# bsides2020.net
KiCad netlist of a schematic drawn in EAGLE
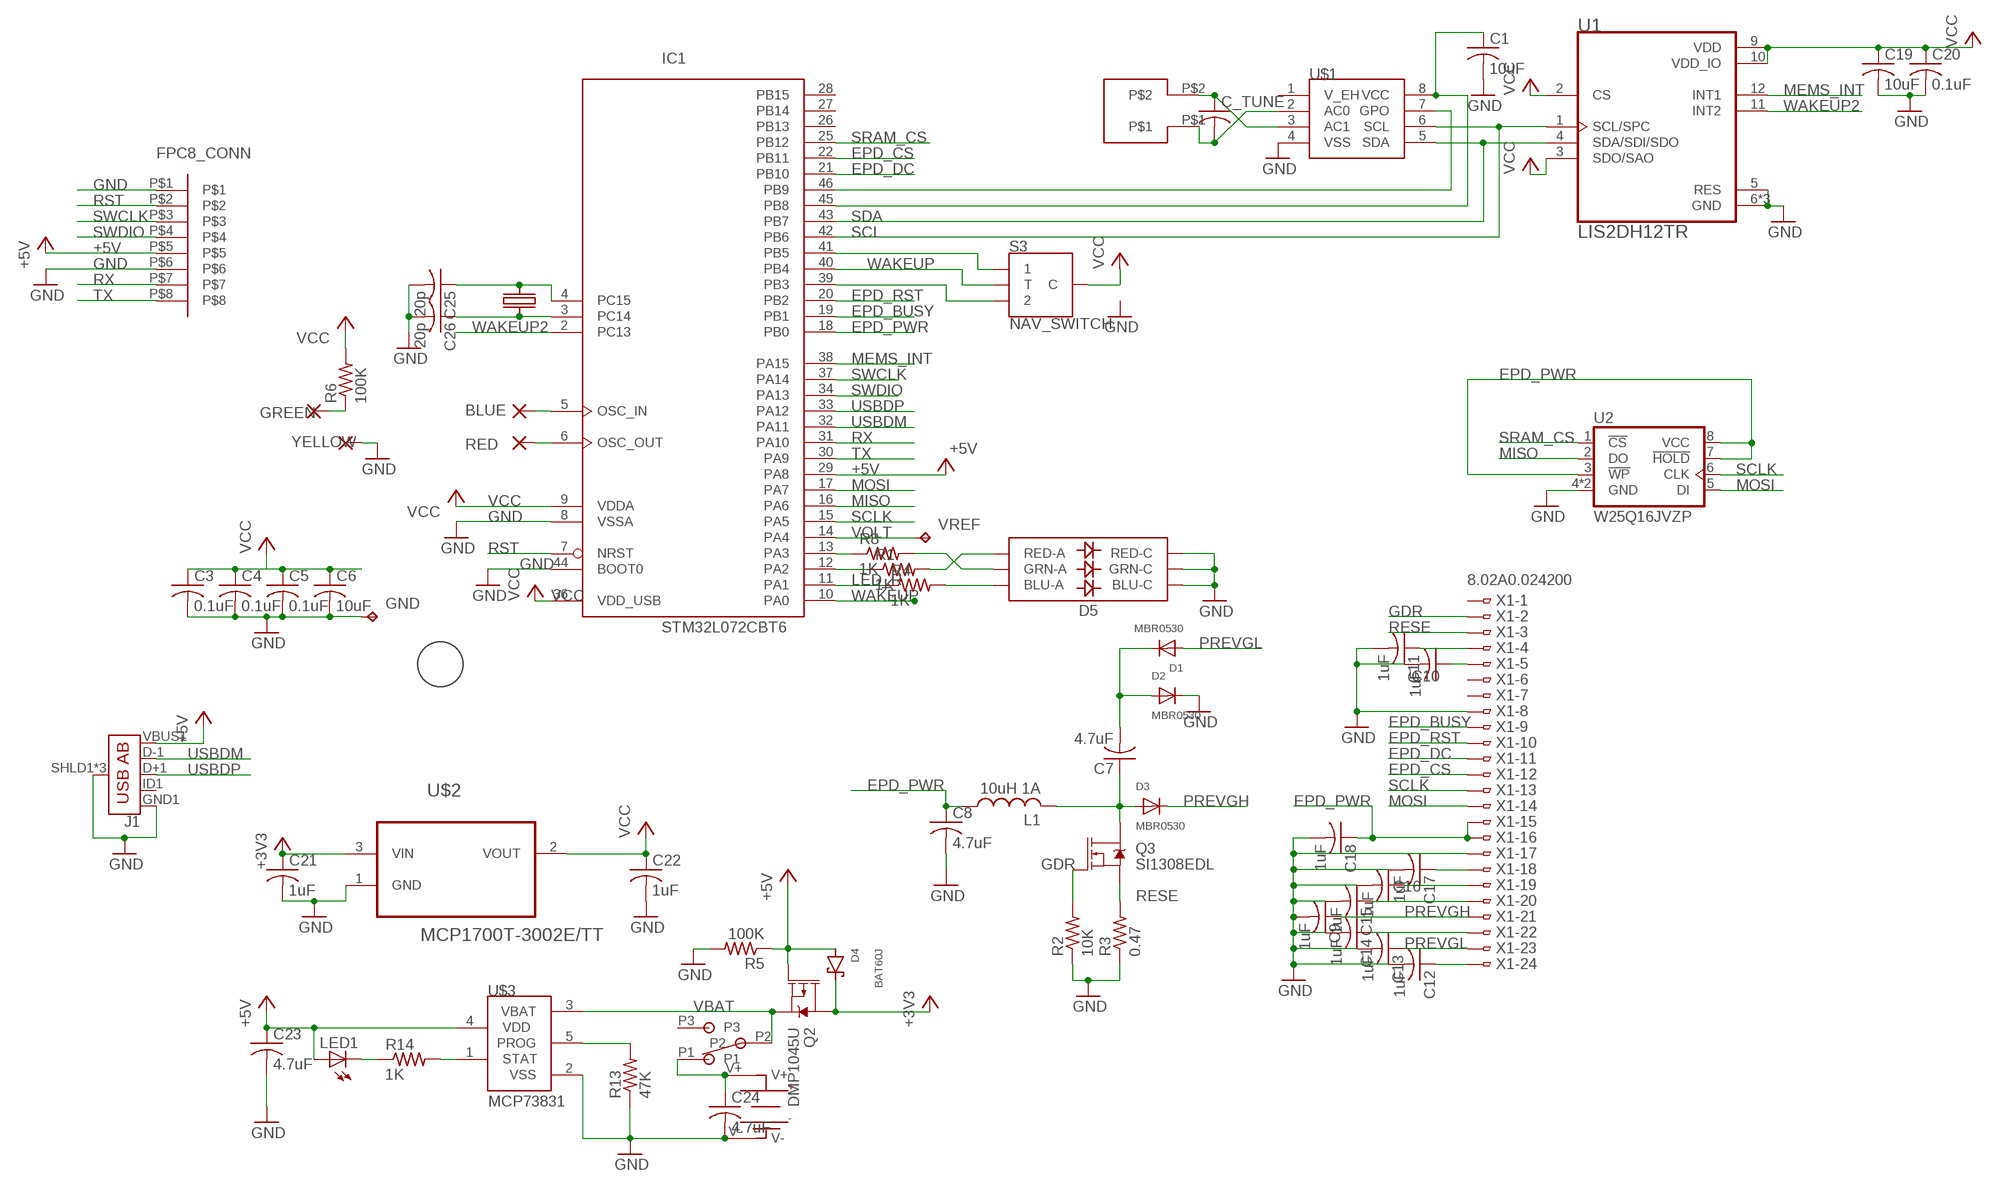
[diagram p0: schematic, sheet 1]

(export (version "E")
  (design (tool "Eeschema 10.0.6"))
  (components
    (comp (ref "BLUE")
      (value "SMD2")
      (footprint "eagle-import:SMD1,27-2,54")
      (libsource (lib "eagle-import") (part "SMD2"))
    )
    (comp (ref "C1")
      (value "10uF")
      (footprint "eagle-import:C0603")
      (libsource (lib "eagle-import") (part "resistor_348_C-USC0603"))
    )
    (comp (ref "C3")
      (value "0.1uF")
      (footprint "eagle-import:C0603")
      (libsource (lib "eagle-import") (part "resistor_348_C-USC0603"))
    )
    (comp (ref "C4")
      (value "0.1uF")
      (footprint "eagle-import:C0603")
      (libsource (lib "eagle-import") (part "resistor_348_C-USC0603"))
    )
    (comp (ref "C5")
      (value "0.1uF")
      (footprint "eagle-import:C0603")
      (libsource (lib "eagle-import") (part "resistor_348_C-USC0603"))
    )
    (comp (ref "C6")
      (value "10uF")
      (footprint "eagle-import:C0603")
      (libsource (lib "eagle-import") (part "resistor_348_C-USC0603"))
    )
    (comp (ref "C7")
      (value "4.7uF")
      (footprint "eagle-import:C0603")
      (libsource (lib "eagle-import") (part "resistor_348_C-USC0603"))
    )
    (comp (ref "C8")
      (value "4.7uF")
      (footprint "eagle-import:C0603")
      (libsource (lib "eagle-import") (part "resistor_348_C-USC0603"))
    )
    (comp (ref "C9")
      (value "1uF")
      (footprint "eagle-import:C0603")
      (libsource (lib "eagle-import") (part "resistor_348_C-USC0603"))
    )
    (comp (ref "C10")
      (value "1uF")
      (footprint "eagle-import:C0603")
      (libsource (lib "eagle-import") (part "resistor_348_C-USC0603"))
    )
    (comp (ref "C11")
      (value "1uF")
      (footprint "eagle-import:C0603")
      (libsource (lib "eagle-import") (part "resistor_348_C-USC0603"))
    )
    (comp (ref "C12")
      (value "1uF")
      (footprint "eagle-import:C0603")
      (libsource (lib "eagle-import") (part "resistor_348_C-USC0603"))
    )
    (comp (ref "C13")
      (value "1uF")
      (footprint "eagle-import:C0603")
      (libsource (lib "eagle-import") (part "resistor_348_C-USC0603"))
    )
    (comp (ref "C14")
      (value "1uF")
      (footprint "eagle-import:C0603")
      (libsource (lib "eagle-import") (part "resistor_348_C-USC0603"))
    )
    (comp (ref "C15")
      (value "1uF")
      (footprint "eagle-import:C0603")
      (libsource (lib "eagle-import") (part "resistor_348_C-USC0603"))
    )
    (comp (ref "C16")
      (value "1uF")
      (footprint "eagle-import:C0603")
      (libsource (lib "eagle-import") (part "resistor_348_C-USC0603"))
    )
    (comp (ref "C17")
      (value "1uF")
      (footprint "eagle-import:C0603")
      (libsource (lib "eagle-import") (part "resistor_348_C-USC0603"))
    )
    (comp (ref "C18")
      (value "1uF")
      (footprint "eagle-import:C0603")
      (libsource (lib "eagle-import") (part "resistor_348_C-USC0603"))
    )
    (comp (ref "C19")
      (value "10uF")
      (footprint "eagle-import:C0603")
      (libsource (lib "eagle-import") (part "resistor_348_C-USC0603"))
    )
    (comp (ref "C20")
      (value "0.1uF")
      (footprint "eagle-import:C0603")
      (libsource (lib "eagle-import") (part "resistor_348_C-USC0603"))
    )
    (comp (ref "C21")
      (value "1uF")
      (footprint "eagle-import:C0603")
      (libsource (lib "eagle-import") (part "resistor_348_C-USC0603"))
    )
    (comp (ref "C22")
      (value "1uF")
      (footprint "eagle-import:C0603")
      (libsource (lib "eagle-import") (part "resistor_348_C-USC0603"))
    )
    (comp (ref "C23")
      (value "4.7uF")
      (footprint "eagle-import:C0603")
      (libsource (lib "eagle-import") (part "resistor_348_C-USC0603"))
    )
    (comp (ref "C24")
      (value "4.7uF")
      (footprint "eagle-import:C0603")
      (libsource (lib "eagle-import") (part "resistor_348_C-USC0603"))
    )
    (comp (ref "C25")
      (value "20p")
      (footprint "eagle-import:C0603")
      (libsource (lib "eagle-import") (part "C-USC0603"))
    )
    (comp (ref "C26")
      (value "20p")
      (footprint "eagle-import:C0603")
      (libsource (lib "eagle-import") (part "C-USC0603"))
    )
    (comp (ref "C_TUNE")
      (value "C-USC0603")
      (footprint "eagle-import:C0603")
      (libsource (lib "eagle-import") (part "resistor_348_C-USC0603"))
    )
    (comp (ref "D1")
      (value "MBR0530")
      (footprint "eagle-import:SOD-123")
      (libsource (lib "eagle-import") (part "DIODESOD-123"))
    )
    (comp (ref "D2")
      (value "MBR0530")
      (footprint "eagle-import:SOD-123")
      (libsource (lib "eagle-import") (part "DIODESOD-123"))
    )
    (comp (ref "D3")
      (value "MBR0530")
      (footprint "eagle-import:SOD-123")
      (libsource (lib "eagle-import") (part "DIODESOD-123"))
    )
    (comp (ref "D4")
      (value "BAT60J")
      (footprint "eagle-import:SOD323_ST")
      (libsource (lib "eagle-import") (part "BAT60J"))
    )
    (comp (ref "D5")
      (value "RGB")
      (footprint "eagle-import:LED-TRICOLOR-5050")
      (libsource (lib "eagle-import") (part "LED-RGBNO_IC"))
    )
    (comp (ref "GND")
      (value "TPB1,27")
      (footprint "eagle-import:B1,27")
      (libsource (lib "eagle-import") (part "TPB1,27"))
    )
    (comp (ref "GREEN")
      (value "SMD2")
      (footprint "eagle-import:SMD1,27-2,54")
      (libsource (lib "eagle-import") (part "SMD2"))
    )
    (comp (ref "IC1")
      (value "STM32L072CBT6")
      (footprint "eagle-import:LQFP48")
      (libsource (lib "eagle-import") (part "STM32L052CT8"))
    )
    (comp (ref "J1")
      (value "USB_AB_SMT")
      (footprint "eagle-import:USB-AB-MICRO-SMD")
      (libsource (lib "eagle-import") (part "USB_AB_SMT"))
    )
    (comp (ref "L1")
      (value "10uH 1A")
      (footprint "eagle-import:L2825P")
      (libsource (lib "eagle-import") (part "L-USL2825P"))
    )
    (comp (ref "LED1")
      (value "LEDCHIPLED_0603")
      (footprint "eagle-import:CHIPLED_0603")
      (libsource (lib "eagle-import") (part "LEDCHIPLED_0603"))
    )
    (comp (ref "Q2")
      (value "DMP1045U")
      (footprint "eagle-import:SOT23-3")
      (libsource (lib "eagle-import") (part "MOSFET_PCH-IRLML2244"))
    )
    (comp (ref "Q3")
      (value "SI1308EDL")
      (footprint "eagle-import:SOT23-3")
      (libsource (lib "eagle-import") (part "MOSFET-NCH-AO3404A"))
    )
    (comp (ref "R1")
      (value "1K")
      (footprint "eagle-import:R0603")
      (libsource (lib "eagle-import") (part "R-US_R0603"))
    )
    (comp (ref "R2")
      (value "10K")
      (footprint "eagle-import:R0603")
      (libsource (lib "eagle-import") (part "R-US_R0603"))
    )
    (comp (ref "R3")
      (value "0.47")
      (footprint "eagle-import:R0603")
      (libsource (lib "eagle-import") (part "R-US_R0603"))
    )
    (comp (ref "R4")
      (value "1K")
      (footprint "eagle-import:R0603")
      (libsource (lib "eagle-import") (part "R-US_R0603"))
    )
    (comp (ref "R5")
      (value "100K")
      (footprint "eagle-import:R0603")
      (libsource (lib "eagle-import") (part "R-US_R0603"))
    )
    (comp (ref "R6")
      (value "100K")
      (footprint "eagle-import:R0603")
      (libsource (lib "eagle-import") (part "R-US_R0603"))
    )
    (comp (ref "R8")
      (value "1K")
      (footprint "eagle-import:R0603")
      (libsource (lib "eagle-import") (part "R-US_R0603"))
    )
    (comp (ref "R13")
      (value "47K")
      (footprint "eagle-import:R0603")
      (libsource (lib "eagle-import") (part "R-US_R0603"))
    )
    (comp (ref "R14")
      (value "1K")
      (footprint "eagle-import:R0603")
      (libsource (lib "eagle-import") (part "R-US_R0603"))
    )
    (comp (ref "RED")
      (value "SMD2")
      (footprint "eagle-import:SMD1,27-2,54")
      (libsource (lib "eagle-import") (part "SMD2"))
    )
    (comp (ref "S3")
      (value "NAV_SWITCH")
      (footprint "eagle-import:NAV_SWITCH")
      (libsource (lib "eagle-import") (part "NAV_SWITCH"))
    )
    (comp (ref "U$1")
      (value "ST25DV04K-IER6S3")
      (footprint "eagle-import:SOIC127P600X175-8N")
      (libsource (lib "eagle-import") (part "ST25DV04K-IER6S3"))
    )
    (comp (ref "U$2")
      (value "MCP1700T-3002E/TT")
      (footprint "eagle-import:SOT95P237X112-3N")
      (fields (field (name "MPN") "MCP1700T-3302E/TT"))
      (libsource (lib "eagle-import") (part "MCP1700T-3302E/TT"))
    )
    (comp (ref "U$3")
      (value "MCP73831")
      (footprint "eagle-import:SOT23-5L")
      (libsource (lib "eagle-import") (part "MCP73831"))
    )
    (comp (ref "U$4")
      (value "ANTANT2")
      (footprint "eagle-import:ANT2")
      (libsource (lib "eagle-import") (part "ANTANT2"))
    )
    (comp (ref "U$6")
      (value "20MM_BATTERY180")
      (footprint "eagle-import:20MM_BATTERY_SMD2")
      (libsource (lib "eagle-import") (part "20MM_BATTERY180"))
    )
    (comp (ref "U$7")
      (value "FPC8_END")
      (footprint "eagle-import:FPC8_END")
      (libsource (lib "eagle-import") (part "FPC8_END"))
    )
    (comp (ref "U$8")
      (value "PLUM")
      (footprint "eagle-import:PLUM")
      (libsource (lib "eagle-import") (part "PLUM"))
    )
    (comp (ref "U$9")
      (value "MSK12C02")
      (footprint "eagle-import:MSK12C02")
      (libsource (lib "eagle-import") (part "MSK12C02"))
    )
    (comp (ref "U$11")
      (value "MC-306 32.7680K-A0:ROHS")
      (footprint "eagle-import:32KHZCRYSTAL")
      (libsource (lib "eagle-import") (part "32KHZCRYSTAL"))
    )
    (comp (ref "U1")
      (value "LIS2DH12TR")
      (footprint "eagle-import:LGA-12N")
      (libsource (lib "eagle-import") (part "LIS2DH12TRLARGE"))
    )
    (comp (ref "U2")
      (value "W25Q16JVZP")
      (footprint "eagle-import:WSON8")
      (libsource (lib "eagle-import") (part "W25Q16BVZP"))
    )
    (comp (ref "VREF")
      (value "TPB1,27")
      (footprint "eagle-import:B1,27")
      (libsource (lib "eagle-import") (part "TPB1,27"))
    )
    (comp (ref "X1")
      (value "8.02A0.024200")
      (footprint "eagle-import:FPC24")
      (libsource (lib "eagle-import") (part "FH12-24S-0.5S"))
    )
    (comp (ref "YELLOW")
      (value "SMD2")
      (footprint "eagle-import:SMD1,27-2,54")
      (libsource (lib "eagle-import") (part "SMD2"))
    )
  )
  (nets
    (net (code "1") (name "+3V3") (class "Default")
      (node (ref "C21") (pin "1") (pinfunction "1_1") (pintype "passive"))
      (node (ref "D4") (pin "C") (pinfunction "C_C") (pintype "passive"))
      (node (ref "Q2") (pin "3") (pinfunction "D_3") (pintype "bidirectional"))
      (node (ref "U$2") (pin "3") (pinfunction "VIN_3") (pintype "input"))
    )
    (net (code "2") (name "+5V") (class "Default")
      (node (ref "C23") (pin "1") (pinfunction "1_1") (pintype "passive"))
      (node (ref "D4") (pin "A") (pinfunction "A_A") (pintype "passive"))
      (node (ref "IC1") (pin "29") (pinfunction "PA8_29") (pintype "bidirectional"))
      (node (ref "J1") (pin "VBUS1") (pinfunction "VBUS_VBUS1") (pintype "power_in"))
      (node (ref "LED1") (pin "A") (pinfunction "A_A") (pintype "passive"))
      (node (ref "Q2") (pin "1") (pinfunction "G_1") (pintype "bidirectional"))
      (node (ref "R5") (pin "1") (pinfunction "1_1") (pintype "passive"))
      (node (ref "U$3") (pin "4") (pinfunction "VDD_4") (pintype "bidirectional"))
      (node (ref "U$7") (pin "P$5") (pinfunction "P$5_P$5") (pintype "bidirectional"))
    )
    (net (code "3") (name "/EPD_BUSY") (class "Default")
      (node (ref "IC1") (pin "19") (pinfunction "PB1_19") (pintype "bidirectional"))
      (node (ref "X1") (pin "P$9") (pinfunction "1_P$9") (pintype "passive"))
    )
    (net (code "4") (name "/EPD_CS") (class "Default")
      (node (ref "IC1") (pin "22") (pinfunction "PB11_22") (pintype "bidirectional"))
      (node (ref "X1") (pin "P$12") (pinfunction "1_P$12") (pintype "passive"))
    )
    (net (code "5") (name "/EPD_DC") (class "Default")
      (node (ref "IC1") (pin "21") (pinfunction "PB10_21") (pintype "bidirectional"))
      (node (ref "X1") (pin "P$11") (pinfunction "1_P$11") (pintype "passive"))
    )
    (net (code "6") (name "/EPD_PWR") (class "Default")
      (node (ref "C18") (pin "1") (pinfunction "1_1") (pintype "passive"))
      (node (ref "C8") (pin "1") (pinfunction "1_1") (pintype "passive"))
      (node (ref "IC1") (pin "18") (pinfunction "PB0_18") (pintype "bidirectional"))
      (node (ref "L1") (pin "1") (pinfunction "1_1") (pintype "passive"))
      (node (ref "U2") (pin "3") (pinfunction "~{WP}_3") (pintype "input"))
      (node (ref "U2") (pin "7") (pinfunction "~{HOLD}_7") (pintype "input"))
      (node (ref "U2") (pin "8") (pinfunction "VCC_8") (pintype "power_in"))
      (node (ref "X1") (pin "P$15") (pinfunction "1_P$15") (pintype "passive"))
      (node (ref "X1") (pin "P$16") (pinfunction "1_P$16") (pintype "passive"))
    )
    (net (code "7") (name "/EPD_RST") (class "Default")
      (node (ref "IC1") (pin "20") (pinfunction "PB2_20") (pintype "bidirectional"))
      (node (ref "X1") (pin "P$10") (pinfunction "1_P$10") (pintype "passive"))
    )
    (net (code "8") (name "/GDR") (class "Default")
      (node (ref "Q3") (pin "1") (pinfunction "G_1") (pintype "bidirectional"))
      (node (ref "R2") (pin "2") (pinfunction "2_2") (pintype "passive"))
      (node (ref "X1") (pin "P$2") (pinfunction "1_P$2") (pintype "passive"))
    )
    (net (code "9") (name "/LED_R") (class "Default")
      (node (ref "IC1") (pin "11") (pinfunction "PA1_11") (pintype "bidirectional"))
      (node (ref "R4") (pin "1") (pinfunction "1_1") (pintype "passive"))
    )
    (net (code "10") (name "/MEMS_INT") (class "Default")
      (node (ref "IC1") (pin "38") (pinfunction "PA15_38") (pintype "bidirectional"))
      (node (ref "U1") (pin "12") (pinfunction "INT1_12") (pintype "output"))
    )
    (net (code "11") (name "/MISO") (class "Default")
      (node (ref "IC1") (pin "16") (pinfunction "PA6_16") (pintype "bidirectional"))
      (node (ref "U2") (pin "2") (pinfunction "DO_2") (pintype "output"))
    )
    (net (code "12") (name "/MOSI") (class "Default")
      (node (ref "IC1") (pin "17") (pinfunction "PA7_17") (pintype "bidirectional"))
      (node (ref "U2") (pin "5") (pinfunction "DI_5") (pintype "input"))
      (node (ref "X1") (pin "P$14") (pinfunction "1_P$14") (pintype "passive"))
    )
    (net (code "13") (name "/PREVGH") (class "Default")
      (node (ref "C9") (pin "1") (pinfunction "1_1") (pintype "passive"))
      (node (ref "D3") (pin "C") (pinfunction "C_C") (pintype "passive"))
      (node (ref "X1") (pin "P$21") (pinfunction "1_P$21") (pintype "passive"))
    )
    (net (code "14") (name "/PREVGL") (class "Default")
      (node (ref "C13") (pin "1") (pinfunction "1_1") (pintype "passive"))
      (node (ref "D1") (pin "A") (pinfunction "A_A") (pintype "passive"))
      (node (ref "X1") (pin "P$23") (pinfunction "1_P$23") (pintype "passive"))
    )
    (net (code "15") (name "/RESE") (class "Default")
      (node (ref "Q3") (pin "2") (pinfunction "S_2") (pintype "bidirectional"))
      (node (ref "R3") (pin "2") (pinfunction "2_2") (pintype "passive"))
      (node (ref "X1") (pin "P$3") (pinfunction "1_P$3") (pintype "passive"))
    )
    (net (code "16") (name "/RST") (class "Default")
      (node (ref "IC1") (pin "7") (pinfunction "NRST_7") (pintype "bidirectional"))
      (node (ref "U$7") (pin "P$2") (pinfunction "P$2_P$2") (pintype "bidirectional"))
    )
    (net (code "17") (name "/RX") (class "Default")
      (node (ref "IC1") (pin "31") (pinfunction "PA10_31") (pintype "bidirectional"))
      (node (ref "U$7") (pin "P$7") (pinfunction "P$7_P$7") (pintype "bidirectional"))
    )
    (net (code "18") (name "/SCL") (class "Default")
      (node (ref "IC1") (pin "42") (pinfunction "PB6_42") (pintype "bidirectional"))
      (node (ref "U$1") (pin "6") (pinfunction "SCL_6") (pintype "bidirectional"))
      (node (ref "U1") (pin "1") (pinfunction "SCL/SPC_1") (pintype "bidirectional"))
    )
    (net (code "19") (name "/SCLK") (class "Default")
      (node (ref "IC1") (pin "15") (pinfunction "PA5_15") (pintype "bidirectional"))
      (node (ref "U2") (pin "6") (pinfunction "CLK_6") (pintype "input"))
      (node (ref "X1") (pin "P$13") (pinfunction "1_P$13") (pintype "passive"))
    )
    (net (code "20") (name "/SDA") (class "Default")
      (node (ref "IC1") (pin "43") (pinfunction "PB7_43") (pintype "bidirectional"))
      (node (ref "U$1") (pin "5") (pinfunction "SDA_5") (pintype "bidirectional"))
      (node (ref "U1") (pin "4") (pinfunction "SDA/SDI/SDO_4") (pintype "bidirectional"))
    )
    (net (code "21") (name "/SRAM_CS") (class "Default")
      (node (ref "IC1") (pin "25") (pinfunction "PB12_25") (pintype "bidirectional"))
      (node (ref "U2") (pin "1") (pinfunction "~{CS}_1") (pintype "input"))
    )
    (net (code "22") (name "/SWCLK") (class "Default")
      (node (ref "IC1") (pin "37") (pinfunction "PA14_37") (pintype "bidirectional"))
      (node (ref "U$7") (pin "P$3") (pinfunction "P$3_P$3") (pintype "bidirectional"))
    )
    (net (code "23") (name "/SWDIO") (class "Default")
      (node (ref "IC1") (pin "34") (pinfunction "PA13_34") (pintype "bidirectional"))
      (node (ref "U$7") (pin "P$4") (pinfunction "P$4_P$4") (pintype "bidirectional"))
    )
    (net (code "24") (name "/TX") (class "Default")
      (node (ref "IC1") (pin "30") (pinfunction "PA9_30") (pintype "bidirectional"))
      (node (ref "U$7") (pin "P$8") (pinfunction "P$8_P$8") (pintype "bidirectional"))
    )
    (net (code "25") (name "/USBDM") (class "Default")
      (node (ref "IC1") (pin "32") (pinfunction "PA11_32") (pintype "bidirectional"))
      (node (ref "J1") (pin "D-1") (pinfunction "D-_D-1") (pintype "bidirectional"))
    )
    (net (code "26") (name "/USBDP") (class "Default")
      (node (ref "IC1") (pin "33") (pinfunction "PA12_33") (pintype "bidirectional"))
      (node (ref "J1") (pin "D+1") (pinfunction "D+_D+1") (pintype "bidirectional"))
    )
    (net (code "27") (name "/VBAT") (class "Default")
      (node (ref "Q2") (pin "2") (pinfunction "S_2") (pintype "bidirectional"))
      (node (ref "U$3") (pin "3") (pinfunction "VBAT_3") (pintype "bidirectional"))
      (node (ref "U$9") (pin "P2") (pinfunction "P2_P2") (pintype "bidirectional"))
    )
    (net (code "28") (name "/VOLT") (class "Default")
      (node (ref "IC1") (pin "14") (pinfunction "PA4_14") (pintype "bidirectional"))
      (node (ref "VREF") (pin "TP") (pinfunction "TP_TP") (pintype "input"))
    )
    (net (code "29") (name "/WAKEUP") (class "Default")
      (node (ref "IC1") (pin "10") (pinfunction "PA0_10") (pintype "bidirectional"))
      (node (ref "IC1") (pin "40") (pinfunction "PB4_40") (pintype "bidirectional"))
      (node (ref "S3") (pin "T") (pinfunction "T_T") (pintype "input"))
    )
    (net (code "30") (name "/WAKEUP2") (class "Default")
      (node (ref "IC1") (pin "2") (pinfunction "PC13_2") (pintype "bidirectional"))
      (node (ref "U1") (pin "11") (pinfunction "INT2_11") (pintype "output"))
    )
    (net (code "31") (name "GND") (class "Default")
      (node (ref "C1") (pin "2") (pinfunction "2_2") (pintype "passive"))
      (node (ref "C10") (pin "2") (pinfunction "2_2") (pintype "passive"))
      (node (ref "C11") (pin "2") (pinfunction "2_2") (pintype "passive"))
      (node (ref "C12") (pin "2") (pinfunction "2_2") (pintype "passive"))
      (node (ref "C13") (pin "2") (pinfunction "2_2") (pintype "passive"))
      (node (ref "C14") (pin "2") (pinfunction "2_2") (pintype "passive"))
      (node (ref "C15") (pin "2") (pinfunction "2_2") (pintype "passive"))
      (node (ref "C16") (pin "2") (pinfunction "2_2") (pintype "passive"))
      (node (ref "C17") (pin "2") (pinfunction "2_2") (pintype "passive"))
      (node (ref "C18") (pin "2") (pinfunction "2_2") (pintype "passive"))
      (node (ref "C19") (pin "2") (pinfunction "2_2") (pintype "passive"))
      (node (ref "C20") (pin "2") (pinfunction "2_2") (pintype "passive"))
      (node (ref "C21") (pin "2") (pinfunction "2_2") (pintype "passive"))
      (node (ref "C22") (pin "2") (pinfunction "2_2") (pintype "passive"))
      (node (ref "C23") (pin "2") (pinfunction "2_2") (pintype "passive"))
      (node (ref "C24") (pin "2") (pinfunction "2_2") (pintype "passive"))
      (node (ref "C25") (pin "2") (pinfunction "2_2") (pintype "passive"))
      (node (ref "C26") (pin "2") (pinfunction "2_2") (pintype "passive"))
      (node (ref "C3") (pin "2") (pinfunction "2_2") (pintype "passive"))
      (node (ref "C4") (pin "2") (pinfunction "2_2") (pintype "passive"))
      (node (ref "C5") (pin "2") (pinfunction "2_2") (pintype "passive"))
      (node (ref "C6") (pin "2") (pinfunction "2_2") (pintype "passive"))
      (node (ref "C8") (pin "2") (pinfunction "2_2") (pintype "passive"))
      (node (ref "C9") (pin "2") (pinfunction "2_2") (pintype "passive"))
      (node (ref "D2") (pin "C") (pinfunction "C_C") (pintype "passive"))
      (node (ref "D5") (pin "4") (pinfunction "BLU-C_4") (pintype "bidirectional"))
      (node (ref "D5") (pin "5") (pinfunction "RED-C_5") (pintype "bidirectional"))
      (node (ref "D5") (pin "6") (pinfunction "GRN-C_6") (pintype "bidirectional"))
      (node (ref "GND") (pin "TP") (pinfunction "TP_TP") (pintype "input"))
      (node (ref "IC1") (pin "44") (pinfunction "BOOT0_44") (pintype "input"))
      (node (ref "IC1") (pin "8") (pinfunction "VSSA_8") (pintype "power_in"))
      (node (ref "J1") (pin "GND1") (pinfunction "GND_GND1") (pintype "power_in"))
      (node (ref "J1") (pin "SHLD1") (pinfunction "SHIELD_SHLD1") (pintype "bidirectional"))
      (node (ref "J1") (pin "SHLD2") (pinfunction "SHIELD_SHLD2") (pintype "bidirectional"))
      (node (ref "J1") (pin "SHLD3") (pinfunction "SHIELD_SHLD3") (pintype "bidirectional"))
      (node (ref "R13") (pin "1") (pinfunction "1_1") (pintype "passive"))
      (node (ref "R2") (pin "1") (pinfunction "1_1") (pintype "passive"))
      (node (ref "R3") (pin "1") (pinfunction "1_1") (pintype "passive"))
      (node (ref "R5") (pin "2") (pinfunction "2_2") (pintype "passive"))
      (node (ref "U$1") (pin "4") (pinfunction "VSS_4") (pintype "bidirectional"))
      (node (ref "U$2") (pin "1") (pinfunction "GND_1") (pintype "passive"))
      (node (ref "U$3") (pin "2") (pinfunction "VSS_2") (pintype "bidirectional"))
      (node (ref "U$6") (pin "V-") (pinfunction "V-_V-") (pintype "bidirectional"))
      (node (ref "U$7") (pin "P$1") (pinfunction "P$1_P$1") (pintype "bidirectional"))
      (node (ref "U$7") (pin "P$6") (pinfunction "P$6_P$6") (pintype "bidirectional"))
      (node (ref "U1") (pin "5") (pinfunction "RES_5") (pintype "power_in"))
      (node (ref "U1") (pin "6") (pinfunction "GND_6") (pintype "power_in"))
      (node (ref "U1") (pin "7") (pinfunction "GND_7") (pintype "power_in"))
      (node (ref "U1") (pin "8") (pinfunction "GND_8") (pintype "power_in"))
      (node (ref "U2") (pin "4") (pinfunction "GND_4") (pintype "power_in"))
      (node (ref "U2") (pin "9") (pinfunction "GND_9") (pintype "power_in"))
      (node (ref "X1") (pin "P$17") (pinfunction "1_P$17") (pintype "passive"))
      (node (ref "X1") (pin "P$8") (pinfunction "1_P$8") (pintype "passive"))
      (node (ref "YELLOW") (pin "1") (pinfunction "P_1") (pintype "passive"))
    )
    (net (code "32") (name "Net-(BLUE-P)") (class "Default")
      (node (ref "BLUE") (pin "1") (pinfunction "P_1") (pintype "passive"))
      (node (ref "IC1") (pin "5") (pinfunction "OSC_IN_5") (pintype "bidirectional"))
    )
    (net (code "33") (name "Net-(C7-Pad2)") (class "Default")
      (node (ref "C7") (pin "2") (pinfunction "2_2") (pintype "passive"))
      (node (ref "D1") (pin "C") (pinfunction "C_C") (pintype "passive"))
      (node (ref "D2") (pin "A") (pinfunction "A_A") (pintype "passive"))
    )
    (net (code "34") (name "Net-(C24-Pad1)") (class "Default")
      (node (ref "C24") (pin "1") (pinfunction "1_1") (pintype "passive"))
      (node (ref "U$6") (pin "V+") (pinfunction "V+_V+") (pintype "bidirectional"))
      (node (ref "U$9") (pin "P1") (pinfunction "P1_P1") (pintype "bidirectional"))
    )
    (net (code "35") (name "Net-(D5-BLU-A)") (class "Default")
      (node (ref "D5") (pin "3") (pinfunction "BLU-A_3") (pintype "bidirectional"))
      (node (ref "R4") (pin "2") (pinfunction "2_2") (pintype "passive"))
    )
    (net (code "36") (name "Net-(D5-GRN-A)") (class "Default")
      (node (ref "D5") (pin "1") (pinfunction "GRN-A_1") (pintype "bidirectional"))
      (node (ref "R8") (pin "2") (pinfunction "2_2") (pintype "passive"))
    )
    (net (code "37") (name "Net-(D5-RED-A)") (class "Default")
      (node (ref "D5") (pin "2") (pinfunction "RED-A_2") (pintype "bidirectional"))
      (node (ref "R1") (pin "2") (pinfunction "2_2") (pintype "passive"))
    )
    (net (code "38") (name "Net-(GREEN-P)") (class "Default")
      (node (ref "GREEN") (pin "1") (pinfunction "P_1") (pintype "passive"))
      (node (ref "R6") (pin "1") (pinfunction "1_1") (pintype "passive"))
    )
    (net (code "39") (name "Net-(IC1A-OSC_OUT)") (class "Default")
      (node (ref "IC1") (pin "6") (pinfunction "OSC_OUT_6") (pintype "bidirectional"))
      (node (ref "RED") (pin "1") (pinfunction "P_1") (pintype "passive"))
    )
    (net (code "40") (name "Net-(IC1A-PA2)") (class "Default")
      (node (ref "IC1") (pin "12") (pinfunction "PA2_12") (pintype "bidirectional"))
      (node (ref "R1") (pin "1") (pinfunction "1_1") (pintype "passive"))
    )
    (net (code "41") (name "Net-(IC1A-PA3)") (class "Default")
      (node (ref "IC1") (pin "13") (pinfunction "PA3_13") (pintype "bidirectional"))
      (node (ref "R8") (pin "1") (pinfunction "1_1") (pintype "passive"))
    )
    (net (code "42") (name "Net-(IC1A-PB3)") (class "Default")
      (node (ref "IC1") (pin "39") (pinfunction "PB3_39") (pintype "bidirectional"))
      (node (ref "S3") (pin "2") (pinfunction "2_2") (pintype "input"))
    )
    (net (code "43") (name "Net-(IC1A-PB5)") (class "Default")
      (node (ref "IC1") (pin "41") (pinfunction "PB5_41") (pintype "bidirectional"))
      (node (ref "S3") (pin "1") (pinfunction "1_1") (pintype "input"))
    )
    (net (code "44") (name "Net-(IC1A-PB8)") (class "Default")
      (node (ref "C1") (pin "1") (pinfunction "1_1") (pintype "passive"))
      (node (ref "IC1") (pin "45") (pinfunction "PB8_45") (pintype "bidirectional"))
      (node (ref "U$1") (pin "8") (pinfunction "VCC_8") (pintype "bidirectional"))
    )
    (net (code "45") (name "Net-(IC1A-PB9)") (class "Default")
      (node (ref "IC1") (pin "46") (pinfunction "PB9_46") (pintype "bidirectional"))
      (node (ref "U$1") (pin "7") (pinfunction "GPO_7") (pintype "bidirectional"))
    )
    (net (code "46") (name "Net-(IC1A-PC14)") (class "Default")
      (node (ref "C26") (pin "1") (pinfunction "1_1") (pintype "passive"))
      (node (ref "IC1") (pin "3") (pinfunction "PC14_3") (pintype "bidirectional"))
      (node (ref "U$11") (pin "P$4") (pinfunction "P$2_P$4") (pintype "bidirectional"))
    )
    (net (code "47") (name "Net-(IC1A-PC15)") (class "Default")
      (node (ref "C25") (pin "1") (pinfunction "1_1") (pintype "passive"))
      (node (ref "IC1") (pin "4") (pinfunction "PC15_4") (pintype "bidirectional"))
      (node (ref "U$11") (pin "P$1") (pinfunction "P$1_P$1") (pintype "bidirectional"))
    )
    (net (code "48") (name "Net-(LED1-PadC)") (class "Default")
      (node (ref "LED1") (pin "C") (pinfunction "C_C") (pintype "passive"))
      (node (ref "R14") (pin "1") (pinfunction "1_1") (pintype "passive"))
    )
    (net (code "49") (name "Net-(Q3-D)") (class "Default")
      (node (ref "C7") (pin "1") (pinfunction "1_1") (pintype "passive"))
      (node (ref "D3") (pin "A") (pinfunction "A_A") (pintype "passive"))
      (node (ref "L1") (pin "2") (pinfunction "2_2") (pintype "passive"))
      (node (ref "Q3") (pin "3") (pinfunction "D_3") (pintype "bidirectional"))
    )
    (net (code "50") (name "Net-(U$1-AC0)") (class "Default")
      (node (ref "C_TUNE") (pin "2") (pinfunction "2_2") (pintype "passive"))
      (node (ref "U$1") (pin "2") (pinfunction "AC0_2") (pintype "bidirectional"))
      (node (ref "U$4") (pin "P$1") (pinfunction "P$1_P$1") (pintype "bidirectional"))
    )
    (net (code "51") (name "Net-(U$1-AC1)") (class "Default")
      (node (ref "C_TUNE") (pin "1") (pinfunction "1_1") (pintype "passive"))
      (node (ref "U$1") (pin "3") (pinfunction "AC1_3") (pintype "bidirectional"))
      (node (ref "U$4") (pin "P$2") (pinfunction "P$2_P$2") (pintype "bidirectional"))
    )
    (net (code "52") (name "Net-(U$3-PROG)") (class "Default")
      (node (ref "R13") (pin "2") (pinfunction "2_2") (pintype "passive"))
      (node (ref "U$3") (pin "5") (pinfunction "PROG_5") (pintype "bidirectional"))
    )
    (net (code "53") (name "Net-(U$3-STAT)") (class "Default")
      (node (ref "R14") (pin "2") (pinfunction "2_2") (pintype "passive"))
      (node (ref "U$3") (pin "1") (pinfunction "STAT_1") (pintype "bidirectional"))
    )
    (net (code "54") (name "Net-(X1J-1)") (class "Default")
      (node (ref "C17") (pin "1") (pinfunction "1_1") (pintype "passive"))
      (node (ref "X1") (pin "P$18") (pinfunction "1_P$18") (pintype "passive"))
    )
    (net (code "55") (name "Net-(X1K-1)") (class "Default")
      (node (ref "C16") (pin "1") (pinfunction "1_1") (pintype "passive"))
      (node (ref "X1") (pin "P$19") (pinfunction "1_P$19") (pintype "passive"))
    )
    (net (code "56") (name "Net-(X1M-1)") (class "Default")
      (node (ref "C15") (pin "1") (pinfunction "1_1") (pintype "passive"))
      (node (ref "X1") (pin "P$20") (pinfunction "1_P$20") (pintype "passive"))
    )
    (net (code "57") (name "Net-(X1O-1)") (class "Default")
      (node (ref "C14") (pin "1") (pinfunction "1_1") (pintype "passive"))
      (node (ref "X1") (pin "P$22") (pinfunction "1_P$22") (pintype "passive"))
    )
    (net (code "58") (name "Net-(X1Q-1)") (class "Default")
      (node (ref "C12") (pin "1") (pinfunction "1_1") (pintype "passive"))
      (node (ref "X1") (pin "P$24") (pinfunction "1_P$24") (pintype "passive"))
    )
    (net (code "59") (name "Net-(X1S-1)") (class "Default")
      (node (ref "C11") (pin "1") (pinfunction "1_1") (pintype "passive"))
      (node (ref "X1") (pin "P$4") (pinfunction "1_P$4") (pintype "passive"))
    )
    (net (code "60") (name "Net-(X1T-1)") (class "Default")
      (node (ref "C10") (pin "1") (pinfunction "1_1") (pintype "passive"))
      (node (ref "X1") (pin "P$5") (pinfunction "1_P$5") (pintype "passive"))
    )
    (net (code "61") (name "VCC") (class "Default")
      (node (ref "C19") (pin "1") (pinfunction "1_1") (pintype "passive"))
      (node (ref "C20") (pin "1") (pinfunction "1_1") (pintype "passive"))
      (node (ref "C22") (pin "1") (pinfunction "1_1") (pintype "passive"))
      (node (ref "C3") (pin "1") (pinfunction "1_1") (pintype "passive"))
      (node (ref "C4") (pin "1") (pinfunction "1_1") (pintype "passive"))
      (node (ref "C5") (pin "1") (pinfunction "1_1") (pintype "passive"))
      (node (ref "C6") (pin "1") (pinfunction "1_1") (pintype "passive"))
      (node (ref "IC1") (pin "36") (pinfunction "VDD_USB_36") (pintype "power_in"))
      (node (ref "IC1") (pin "9") (pinfunction "VDDA_9") (pintype "power_in"))
      (node (ref "R6") (pin "2") (pinfunction "2_2") (pintype "passive"))
      (node (ref "S3") (pin "C") (pinfunction "C_C") (pintype "power_in"))
      (node (ref "U$2") (pin "2") (pinfunction "VOUT_2") (pintype "output"))
      (node (ref "U1") (pin "10") (pinfunction "VDD_IO_10") (pintype "power_in"))
      (node (ref "U1") (pin "2") (pinfunction "CS_2") (pintype "input"))
      (node (ref "U1") (pin "3") (pinfunction "SDO/SAO_3") (pintype "bidirectional"))
      (node (ref "U1") (pin "9") (pinfunction "VDD_9") (pintype "power_in"))
    )
    (net (code "62") (name "unconnected-(IC1A-PB13-Pad26)") (class "Default")
      (node (ref "IC1") (pin "26") (pinfunction "PB13_26") (pintype "bidirectional"))
    )
    (net (code "63") (name "unconnected-(IC1A-PB14-Pad27)") (class "Default")
      (node (ref "IC1") (pin "27") (pinfunction "PB14_27") (pintype "bidirectional"))
    )
    (net (code "64") (name "unconnected-(IC1A-PB15-Pad28)") (class "Default")
      (node (ref "IC1") (pin "28") (pinfunction "PB15_28") (pintype "bidirectional"))
    )
    (net (code "65") (name "unconnected-(J1-USBID-PadID1)") (class "Default")
      (node (ref "J1") (pin "ID1") (pinfunction "USBID_ID1") (pintype "bidirectional"))
    )
    (net (code "66") (name "unconnected-(U$1-V_EH-Pad1)") (class "Default")
      (node (ref "U$1") (pin "1") (pinfunction "V_EH_1") (pintype "bidirectional"))
    )
    (net (code "67") (name "unconnected-(U$9-PadP3)") (class "Default")
      (node (ref "U$9") (pin "P3") (pinfunction "P3_P3") (pintype "bidirectional"))
    )
    (net (code "68") (name "unconnected-(X1A-1-PadP$1)") (class "Default")
      (node (ref "X1") (pin "P$1") (pinfunction "1_P$1") (pintype "passive"))
    )
    (net (code "69") (name "unconnected-(X1U-1-PadP$6)") (class "Default")
      (node (ref "X1") (pin "P$6") (pinfunction "1_P$6") (pintype "passive"))
    )
    (net (code "70") (name "unconnected-(X1V-1-PadP$7)") (class "Default")
      (node (ref "X1") (pin "P$7") (pinfunction "1_P$7") (pintype "passive"))
    )
  )
)
